# USB_FTDI_Prog_Pwr.net
KiCad netlist of a schematic drawn in EAGLE
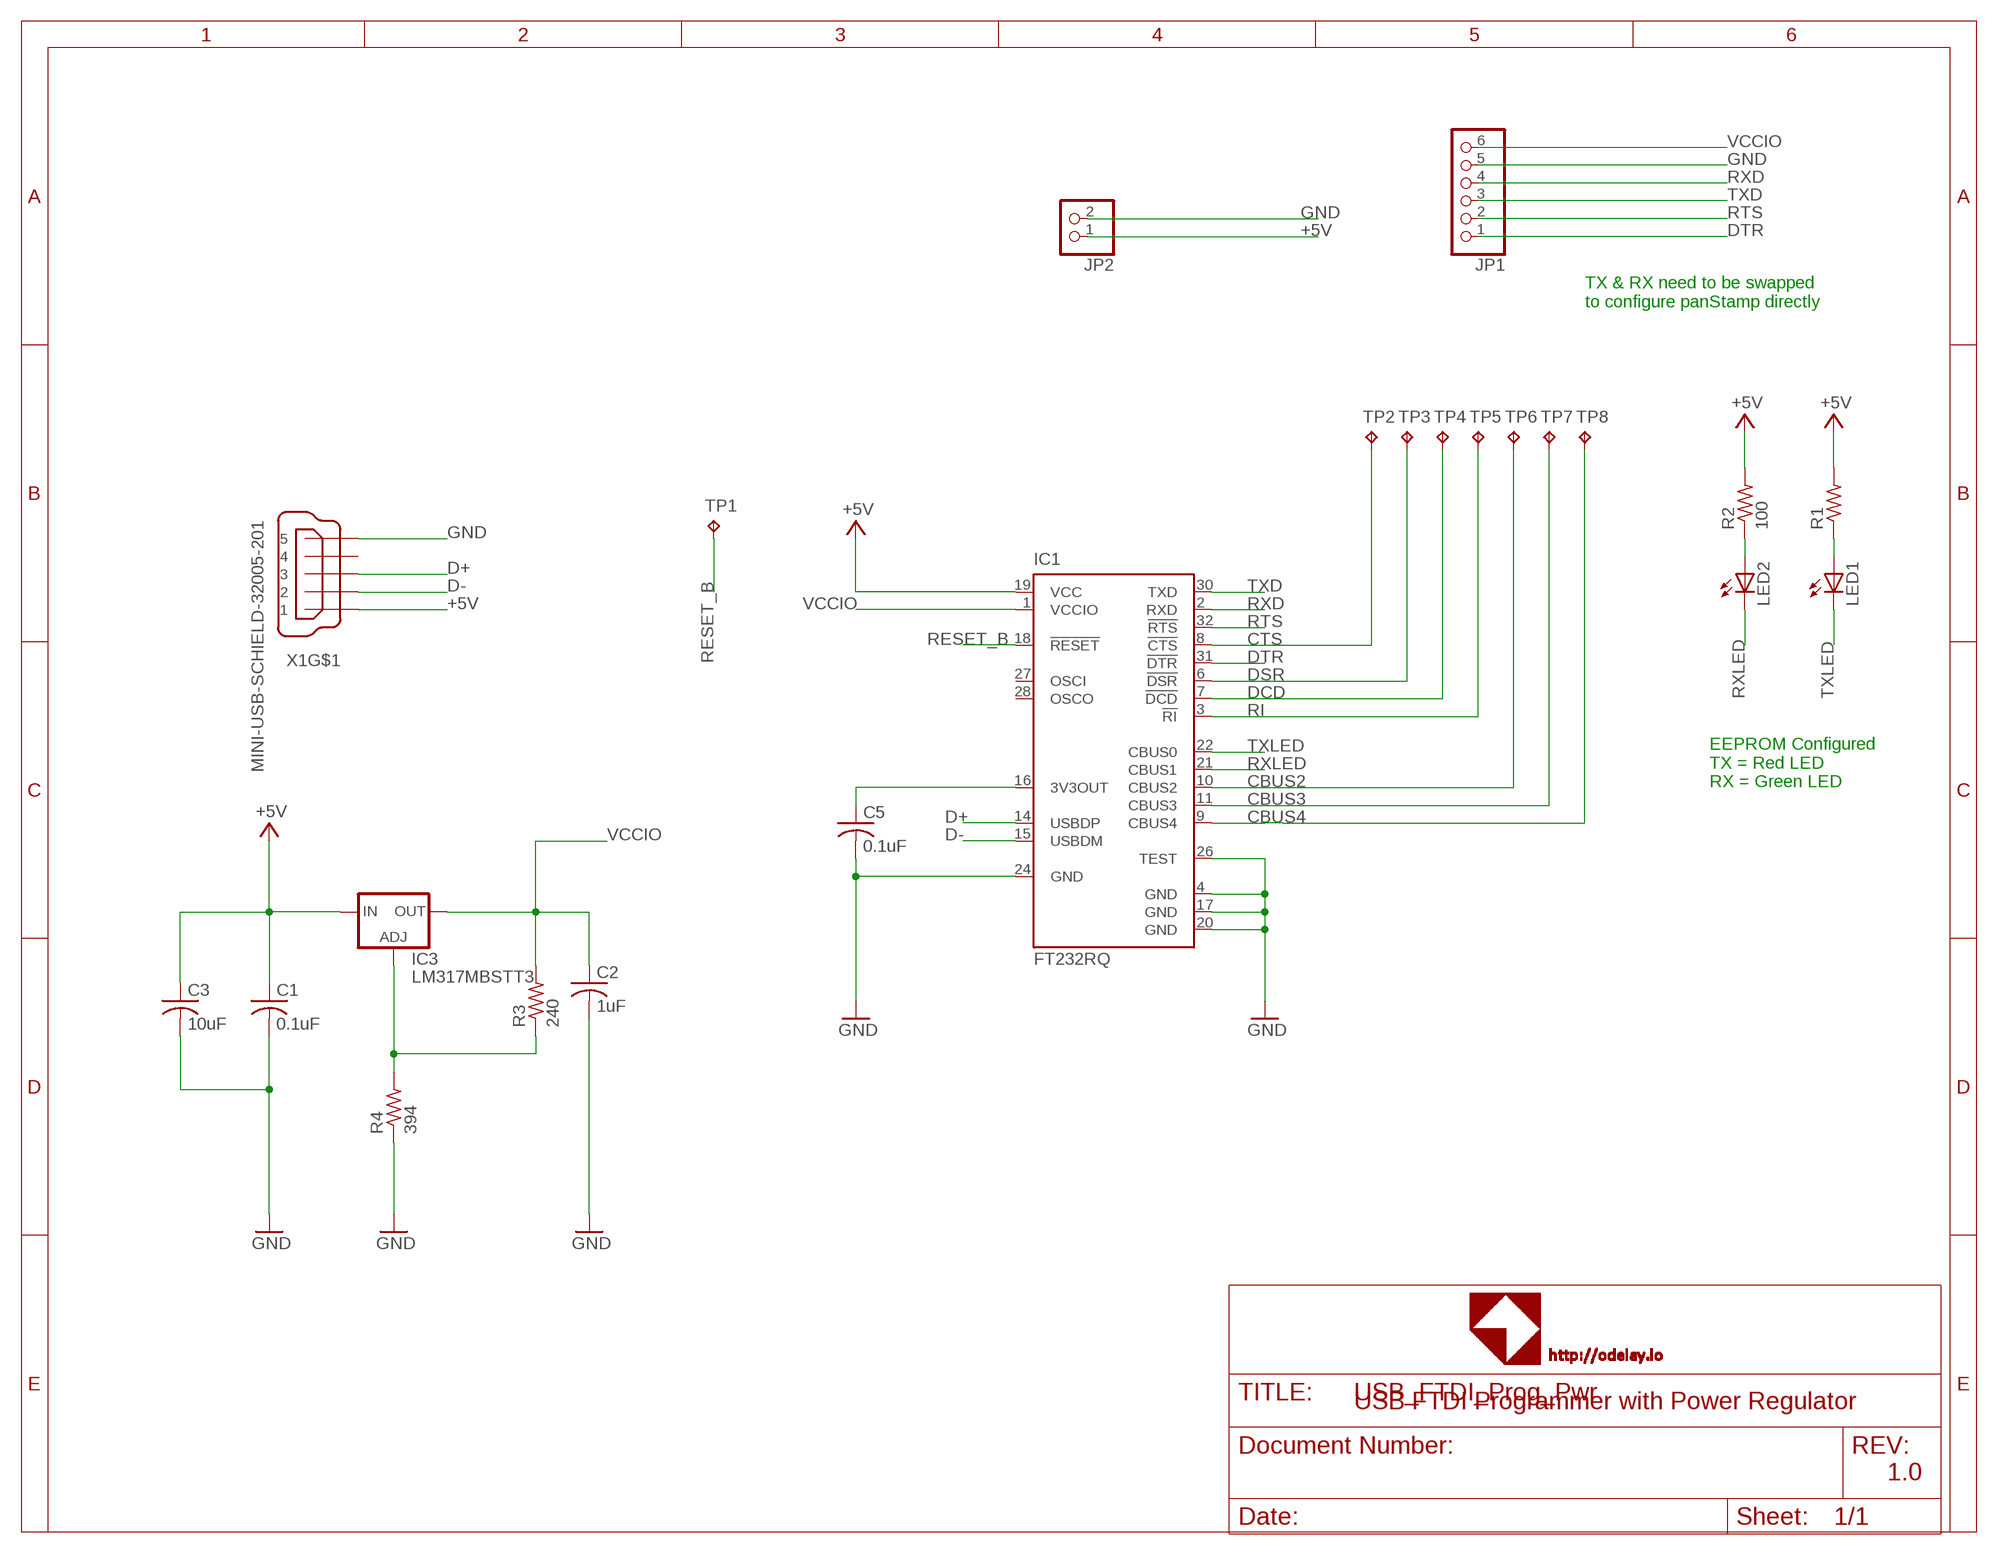
[diagram p0: schematic, sheet 1]

(export (version "E")
  (design (tool "Eeschema 10.0.6"))
  (components
    (comp (ref "C1")
      (value "0.1uF")
      (footprint "eagle-import:C0402")
      (libsource (lib "eagle-import") (part "C-USC0402"))
    )
    (comp (ref "C2")
      (value "1uF")
      (footprint "eagle-import:C0402")
      (libsource (lib "eagle-import") (part "C-USC0402"))
    )
    (comp (ref "C3")
      (value "10uF")
      (footprint "eagle-import:C0603")
      (libsource (lib "eagle-import") (part "C-USC0603"))
    )
    (comp (ref "C5")
      (value "0.1uF")
      (footprint "eagle-import:C0402")
      (libsource (lib "eagle-import") (part "C-USC0402"))
    )
    (comp (ref "IC1")
      (value "FT232RQ")
      (footprint "eagle-import:QFN32")
      (libsource (lib "eagle-import") (part "FT232RQ"))
    )
    (comp (ref "IC3")
      (value "LM317MBSTT3")
      (footprint "eagle-import:SOT223")
      (libsource (lib "eagle-import") (part "LM317?MBSTT3"))
    )
    (comp (ref "JP1")
      (value "PINHD-1X6")
      (footprint "eagle-import:1X06")
      (libsource (lib "eagle-import") (part "PINHD-1X6"))
    )
    (comp (ref "JP2")
      (value "PINHD-1X2")
      (footprint "eagle-import:1X02")
      (libsource (lib "eagle-import") (part "PINHD-1X2"))
    )
    (comp (ref "LED1")
      (value "LEDCHIP-LED0603")
      (footprint "eagle-import:CHIP-LED0603")
      (libsource (lib "eagle-import") (part "LEDCHIP-LED0603"))
    )
    (comp (ref "LED2")
      (value "LEDCHIP-LED0603")
      (footprint "eagle-import:CHIP-LED0603")
      (libsource (lib "eagle-import") (part "LEDCHIP-LED0603"))
    )
    (comp (ref "R1")
      (value "R-US_R0402")
      (footprint "eagle-import:R0402")
      (libsource (lib "eagle-import") (part "R-US_R0402"))
    )
    (comp (ref "R2")
      (value "100")
      (footprint "eagle-import:R0402")
      (libsource (lib "eagle-import") (part "R-US_R0402"))
    )
    (comp (ref "R3")
      (value "240")
      (footprint "eagle-import:R0402")
      (libsource (lib "eagle-import") (part "R-US_R0402"))
    )
    (comp (ref "R4")
      (value "394")
      (footprint "eagle-import:R0402")
      (libsource (lib "eagle-import") (part "R-US_R0402"))
    )
    (comp (ref "TP1")
      (value "TPB1,27")
      (footprint "eagle-import:B1,27")
      (libsource (lib "eagle-import") (part "TPB1,27"))
    )
    (comp (ref "TP2")
      (value "TPB1,27")
      (footprint "eagle-import:B1,27")
      (libsource (lib "eagle-import") (part "TPB1,27"))
    )
    (comp (ref "TP3")
      (value "TPB1,27")
      (footprint "eagle-import:B1,27")
      (libsource (lib "eagle-import") (part "TPB1,27"))
    )
    (comp (ref "TP4")
      (value "TPB1,27")
      (footprint "eagle-import:B1,27")
      (libsource (lib "eagle-import") (part "TPB1,27"))
    )
    (comp (ref "TP5")
      (value "TPB1,27")
      (footprint "eagle-import:B1,27")
      (libsource (lib "eagle-import") (part "TPB1,27"))
    )
    (comp (ref "TP6")
      (value "TPB1,27")
      (footprint "eagle-import:B1,27")
      (libsource (lib "eagle-import") (part "TPB1,27"))
    )
    (comp (ref "TP7")
      (value "TPB1,27")
      (footprint "eagle-import:B1,27")
      (libsource (lib "eagle-import") (part "TPB1,27"))
    )
    (comp (ref "TP8")
      (value "TPB1,27")
      (footprint "eagle-import:B1,27")
      (libsource (lib "eagle-import") (part "TPB1,27"))
    )
    (comp (ref "X1")
      (value "MINI-USB-SCHIELD-32005-201")
      (footprint "eagle-import:32005-201")
      (libsource (lib "eagle-import") (part "MINI-USB-SCHIELD-32005-201"))
    )
  )
  (nets
    (net (code "1") (name "+5V") (class "Default")
      (node (ref "C1") (pin "1") (pinfunction "1_1") (pintype "passive"))
      (node (ref "C3") (pin "1") (pinfunction "1_1") (pintype "passive"))
      (node (ref "IC1") (pin "19") (pinfunction "VCC_19") (pintype "power_in"))
      (node (ref "IC3") (pin "3") (pinfunction "IN_3") (pintype "input"))
      (node (ref "JP2") (pin "1") (pinfunction "1_1") (pintype "passive"))
      (node (ref "R1") (pin "2") (pinfunction "2_2") (pintype "passive"))
      (node (ref "R2") (pin "2") (pinfunction "2_2") (pintype "passive"))
      (node (ref "X1") (pin "1") (pinfunction "1_1") (pintype "passive"))
    )
    (net (code "2") (name "/CBUS2") (class "Default")
      (node (ref "IC1") (pin "10") (pinfunction "CBUS2_10") (pintype "bidirectional"))
      (node (ref "TP6") (pin "TP") (pinfunction "TP_TP") (pintype "input"))
    )
    (net (code "3") (name "/CBUS3") (class "Default")
      (node (ref "IC1") (pin "11") (pinfunction "CBUS3_11") (pintype "bidirectional"))
      (node (ref "TP7") (pin "TP") (pinfunction "TP_TP") (pintype "input"))
    )
    (net (code "4") (name "/CBUS4") (class "Default")
      (node (ref "IC1") (pin "9") (pinfunction "CBUS4_9") (pintype "bidirectional"))
      (node (ref "TP8") (pin "TP") (pinfunction "TP_TP") (pintype "input"))
    )
    (net (code "5") (name "/CTS") (class "Default")
      (node (ref "IC1") (pin "8") (pinfunction "~{CTS}_8") (pintype "input"))
      (node (ref "TP2") (pin "TP") (pinfunction "TP_TP") (pintype "input"))
    )
    (net (code "6") (name "/D+") (class "Default")
      (node (ref "IC1") (pin "14") (pinfunction "USBDP_14") (pintype "bidirectional"))
      (node (ref "X1") (pin "3") (pinfunction "3_3") (pintype "passive"))
    )
    (net (code "7") (name "/D-") (class "Default")
      (node (ref "IC1") (pin "15") (pinfunction "USBDM_15") (pintype "bidirectional"))
      (node (ref "X1") (pin "2") (pinfunction "2_2") (pintype "passive"))
    )
    (net (code "8") (name "/DCD") (class "Default")
      (node (ref "IC1") (pin "7") (pinfunction "~{DCD}_7") (pintype "input"))
      (node (ref "TP4") (pin "TP") (pinfunction "TP_TP") (pintype "input"))
    )
    (net (code "9") (name "/DSR") (class "Default")
      (node (ref "IC1") (pin "6") (pinfunction "~{DSR}_6") (pintype "input"))
      (node (ref "TP3") (pin "TP") (pinfunction "TP_TP") (pintype "input"))
    )
    (net (code "10") (name "/DTR") (class "Default")
      (node (ref "IC1") (pin "31") (pinfunction "~{DTR}_31") (pintype "output"))
      (node (ref "JP1") (pin "1") (pinfunction "1_1") (pintype "passive"))
    )
    (net (code "11") (name "/RESET_B") (class "Default")
      (node (ref "IC1") (pin "18") (pinfunction "~{RESET}_18") (pintype "input"))
      (node (ref "TP1") (pin "TP") (pinfunction "TP_TP") (pintype "input"))
    )
    (net (code "12") (name "/RI") (class "Default")
      (node (ref "IC1") (pin "3") (pinfunction "~{RI}_3") (pintype "input"))
      (node (ref "TP5") (pin "TP") (pinfunction "TP_TP") (pintype "input"))
    )
    (net (code "13") (name "/RTS") (class "Default")
      (node (ref "IC1") (pin "32") (pinfunction "~{RTS}_32") (pintype "output"))
      (node (ref "JP1") (pin "2") (pinfunction "2_2") (pintype "passive"))
    )
    (net (code "14") (name "/RXD") (class "Default")
      (node (ref "IC1") (pin "2") (pinfunction "RXD_2") (pintype "input"))
      (node (ref "JP1") (pin "4") (pinfunction "4_4") (pintype "passive"))
    )
    (net (code "15") (name "/RXLED") (class "Default")
      (node (ref "IC1") (pin "21") (pinfunction "CBUS1_21") (pintype "bidirectional"))
      (node (ref "LED2") (pin "C") (pinfunction "C_C") (pintype "passive"))
    )
    (net (code "16") (name "/TXD") (class "Default")
      (node (ref "IC1") (pin "30") (pinfunction "TXD_30") (pintype "output"))
      (node (ref "JP1") (pin "3") (pinfunction "3_3") (pintype "passive"))
    )
    (net (code "17") (name "/TXLED") (class "Default")
      (node (ref "IC1") (pin "22") (pinfunction "CBUS0_22") (pintype "bidirectional"))
      (node (ref "LED1") (pin "C") (pinfunction "C_C") (pintype "passive"))
    )
    (net (code "18") (name "/VCCIO") (class "Default")
      (node (ref "C2") (pin "1") (pinfunction "1_1") (pintype "passive"))
      (node (ref "IC1") (pin "1") (pinfunction "VCCIO_1") (pintype "power_in"))
      (node (ref "IC3") (pin "4") (pinfunction "OUT_4") (pintype "passive"))
      (node (ref "JP1") (pin "6") (pinfunction "6_6") (pintype "passive"))
      (node (ref "R3") (pin "2") (pinfunction "2_2") (pintype "passive"))
    )
    (net (code "19") (name "GND") (class "Default")
      (node (ref "C1") (pin "2") (pinfunction "2_2") (pintype "passive"))
      (node (ref "C2") (pin "2") (pinfunction "2_2") (pintype "passive"))
      (node (ref "C3") (pin "2") (pinfunction "2_2") (pintype "passive"))
      (node (ref "C5") (pin "2") (pinfunction "2_2") (pintype "passive"))
      (node (ref "IC1") (pin "17") (pinfunction "GND_17") (pintype "power_in"))
      (node (ref "IC1") (pin "20") (pinfunction "GND_20") (pintype "power_in"))
      (node (ref "IC1") (pin "24") (pinfunction "GND_24") (pintype "power_in"))
      (node (ref "IC1") (pin "26") (pinfunction "TEST_26") (pintype "input"))
      (node (ref "IC1") (pin "4") (pinfunction "GND_4") (pintype "power_in"))
      (node (ref "JP1") (pin "5") (pinfunction "5_5") (pintype "passive"))
      (node (ref "JP2") (pin "2") (pinfunction "2_2") (pintype "passive"))
      (node (ref "R4") (pin "1") (pinfunction "1_1") (pintype "passive"))
      (node (ref "X1") (pin "5") (pinfunction "5_5") (pintype "passive"))
    )
    (net (code "20") (name "Net-(IC1-3V3OUT)") (class "Default")
      (node (ref "C5") (pin "1") (pinfunction "1_1") (pintype "passive"))
      (node (ref "IC1") (pin "16") (pinfunction "3V3OUT_16") (pintype "output"))
    )
    (net (code "21") (name "Net-(IC3-ADJ)") (class "Default")
      (node (ref "IC3") (pin "1") (pinfunction "ADJ_1") (pintype "input"))
      (node (ref "R3") (pin "1") (pinfunction "1_1") (pintype "passive"))
      (node (ref "R4") (pin "2") (pinfunction "2_2") (pintype "passive"))
    )
    (net (code "22") (name "Net-(LED1-PadA)") (class "Default")
      (node (ref "LED1") (pin "A") (pinfunction "A_A") (pintype "passive"))
      (node (ref "R1") (pin "1") (pinfunction "1_1") (pintype "passive"))
    )
    (net (code "23") (name "Net-(LED2-PadA)") (class "Default")
      (node (ref "LED2") (pin "A") (pinfunction "A_A") (pintype "passive"))
      (node (ref "R2") (pin "1") (pinfunction "1_1") (pintype "passive"))
    )
    (net (code "24") (name "unconnected-(IC1-OSCI-Pad27)") (class "Default")
      (node (ref "IC1") (pin "27") (pinfunction "OSCI_27") (pintype "input"))
    )
    (net (code "25") (name "unconnected-(IC1-OSCO-Pad28)") (class "Default")
      (node (ref "IC1") (pin "28") (pinfunction "OSCO_28") (pintype "output"))
    )
    (net (code "26") (name "unconnected-(X1-Pad4)") (class "Default")
      (node (ref "X1") (pin "4") (pinfunction "4_4") (pintype "passive"))
    )
  )
)
